# L298_Motor_Driver.net
KiCad netlist of a schematic drawn in EAGLE
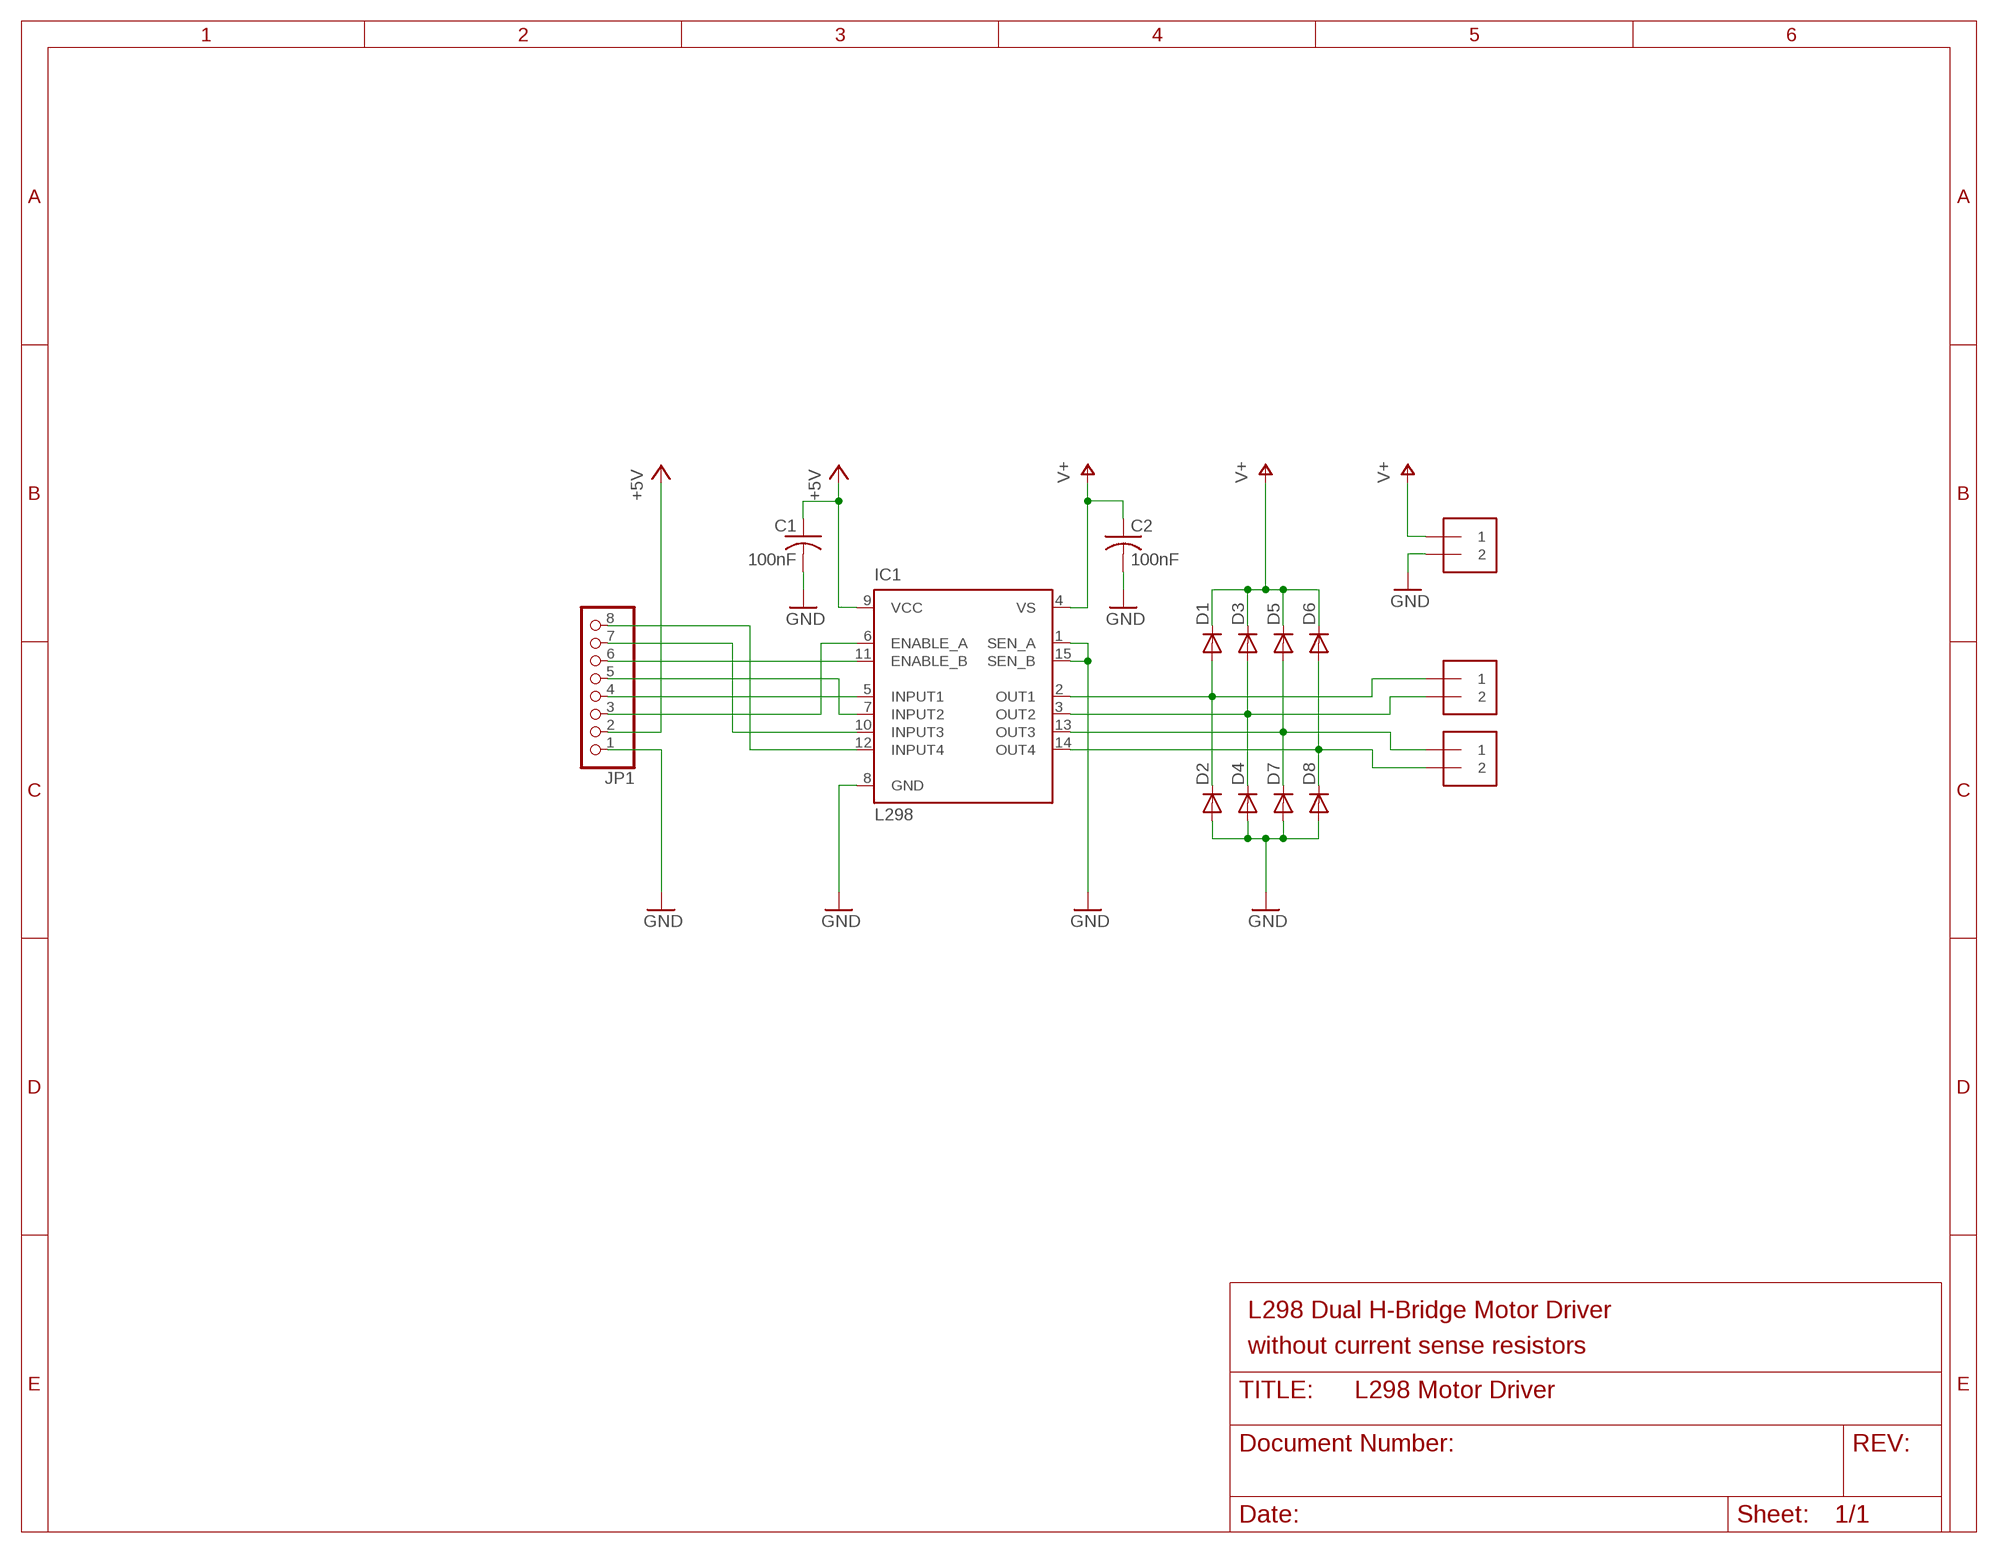
[diagram p0: schematic, sheet 1]

(export (version "E")
  (design (tool "Eeschema 10.0.6"))
  (components
    (comp (ref "C1")
      (value "100nF")
      (footprint "eagle-import:C050-024X044")
      (libsource (lib "eagle-import") (part "C-US050-024X044"))
    )
    (comp (ref "C2")
      (value "100nF")
      (footprint "eagle-import:C050-024X044")
      (libsource (lib "eagle-import") (part "C-US050-024X044"))
    )
    (comp (ref "D1")
      (value "DIODE-D-5")
      (footprint "eagle-import:D-5")
      (libsource (lib "eagle-import") (part "DIODE-D-5"))
    )
    (comp (ref "D2")
      (value "DIODE-D-5")
      (footprint "eagle-import:D-5")
      (libsource (lib "eagle-import") (part "DIODE-D-5"))
    )
    (comp (ref "D3")
      (value "DIODE-D-5")
      (footprint "eagle-import:D-5")
      (libsource (lib "eagle-import") (part "DIODE-D-5"))
    )
    (comp (ref "D4")
      (value "DIODE-D-5")
      (footprint "eagle-import:D-5")
      (libsource (lib "eagle-import") (part "DIODE-D-5"))
    )
    (comp (ref "D5")
      (value "DIODE-D-5")
      (footprint "eagle-import:D-5")
      (libsource (lib "eagle-import") (part "DIODE-D-5"))
    )
    (comp (ref "D6")
      (value "DIODE-D-5")
      (footprint "eagle-import:D-5")
      (libsource (lib "eagle-import") (part "DIODE-D-5"))
    )
    (comp (ref "D7")
      (value "DIODE-D-5")
      (footprint "eagle-import:D-5")
      (libsource (lib "eagle-import") (part "DIODE-D-5"))
    )
    (comp (ref "D8")
      (value "DIODE-D-5")
      (footprint "eagle-import:D-5")
      (libsource (lib "eagle-import") (part "DIODE-D-5"))
    )
    (comp (ref "IC1")
      (value "L298")
      (footprint "eagle-import:MULTIWATT-15")
      (fields (field (name "MPN") "L298N"))
      (libsource (lib "eagle-import") (part "L298"))
    )
    (comp (ref "J1")
      (value "1X2-3.5MM")
      (footprint "eagle-import:1X2-3.5MM")
      (libsource (lib "eagle-import") (part "1X2-3.5MM"))
    )
    (comp (ref "J2")
      (value "1X2-3.5MM")
      (footprint "eagle-import:1X2-3.5MM")
      (libsource (lib "eagle-import") (part "1X2-3.5MM"))
    )
    (comp (ref "J3")
      (value "1X2-3.5MM")
      (footprint "eagle-import:1X2-3.5MM")
      (libsource (lib "eagle-import") (part "1X2-3.5MM"))
    )
    (comp (ref "JP1")
      (value "PINHD-1X8")
      (footprint "eagle-import:1X08")
      (libsource (lib "eagle-import") (part "PINHD-1X8"))
    )
  )
  (nets
    (net (code "1") (name "+5V") (class "Default")
      (node (ref "C1") (pin "1") (pinfunction "1_1") (pintype "passive"))
      (node (ref "IC1") (pin "9") (pinfunction "VCC_9") (pintype "power_in"))
      (node (ref "JP1") (pin "2") (pinfunction "2_2") (pintype "passive"))
    )
    (net (code "2") (name "GND") (class "Default")
      (node (ref "C1") (pin "2") (pinfunction "2_2") (pintype "passive"))
      (node (ref "C2") (pin "2") (pinfunction "2_2") (pintype "passive"))
      (node (ref "D2") (pin "A") (pinfunction "A_A") (pintype "passive"))
      (node (ref "D4") (pin "A") (pinfunction "A_A") (pintype "passive"))
      (node (ref "D7") (pin "A") (pinfunction "A_A") (pintype "passive"))
      (node (ref "D8") (pin "A") (pinfunction "A_A") (pintype "passive"))
      (node (ref "IC1") (pin "1") (pinfunction "SEN_A_1") (pintype "input"))
      (node (ref "IC1") (pin "15") (pinfunction "SEN_B_15") (pintype "input"))
      (node (ref "IC1") (pin "8") (pinfunction "GND_8") (pintype "power_in"))
      (node (ref "J1") (pin "2") (pinfunction "2_2") (pintype "passive"))
      (node (ref "JP1") (pin "1") (pinfunction "1_1") (pintype "passive"))
    )
    (net (code "3") (name "Net-(IC1-ENABLE_A)") (class "Default")
      (node (ref "IC1") (pin "6") (pinfunction "ENABLE_A_6") (pintype "input"))
      (node (ref "JP1") (pin "3") (pinfunction "3_3") (pintype "passive"))
    )
    (net (code "4") (name "Net-(IC1-ENABLE_B)") (class "Default")
      (node (ref "IC1") (pin "11") (pinfunction "ENABLE_B_11") (pintype "input"))
      (node (ref "JP1") (pin "6") (pinfunction "6_6") (pintype "passive"))
    )
    (net (code "5") (name "Net-(IC1-INPUT1)") (class "Default")
      (node (ref "IC1") (pin "5") (pinfunction "INPUT1_5") (pintype "input"))
      (node (ref "JP1") (pin "4") (pinfunction "4_4") (pintype "passive"))
    )
    (net (code "6") (name "Net-(IC1-INPUT2)") (class "Default")
      (node (ref "IC1") (pin "7") (pinfunction "INPUT2_7") (pintype "input"))
      (node (ref "JP1") (pin "5") (pinfunction "5_5") (pintype "passive"))
    )
    (net (code "7") (name "Net-(IC1-INPUT3)") (class "Default")
      (node (ref "IC1") (pin "10") (pinfunction "INPUT3_10") (pintype "input"))
      (node (ref "JP1") (pin "7") (pinfunction "7_7") (pintype "passive"))
    )
    (net (code "8") (name "Net-(IC1-INPUT4)") (class "Default")
      (node (ref "IC1") (pin "12") (pinfunction "INPUT4_12") (pintype "input"))
      (node (ref "JP1") (pin "8") (pinfunction "8_8") (pintype "passive"))
    )
    (net (code "9") (name "Net-(IC1-OUT1)") (class "Default")
      (node (ref "D1") (pin "A") (pinfunction "A_A") (pintype "passive"))
      (node (ref "D2") (pin "C") (pinfunction "C_C") (pintype "passive"))
      (node (ref "IC1") (pin "2") (pinfunction "OUT1_2") (pintype "output"))
      (node (ref "J2") (pin "1") (pinfunction "1_1") (pintype "passive"))
    )
    (net (code "10") (name "Net-(IC1-OUT2)") (class "Default")
      (node (ref "D3") (pin "A") (pinfunction "A_A") (pintype "passive"))
      (node (ref "D4") (pin "C") (pinfunction "C_C") (pintype "passive"))
      (node (ref "IC1") (pin "3") (pinfunction "OUT2_3") (pintype "output"))
      (node (ref "J2") (pin "2") (pinfunction "2_2") (pintype "passive"))
    )
    (net (code "11") (name "Net-(IC1-OUT3)") (class "Default")
      (node (ref "D5") (pin "A") (pinfunction "A_A") (pintype "passive"))
      (node (ref "D7") (pin "C") (pinfunction "C_C") (pintype "passive"))
      (node (ref "IC1") (pin "13") (pinfunction "OUT3_13") (pintype "output"))
      (node (ref "J3") (pin "1") (pinfunction "1_1") (pintype "passive"))
    )
    (net (code "12") (name "Net-(IC1-OUT4)") (class "Default")
      (node (ref "D6") (pin "A") (pinfunction "A_A") (pintype "passive"))
      (node (ref "D8") (pin "C") (pinfunction "C_C") (pintype "passive"))
      (node (ref "IC1") (pin "14") (pinfunction "OUT4_14") (pintype "output"))
      (node (ref "J3") (pin "2") (pinfunction "2_2") (pintype "passive"))
    )
    (net (code "13") (name "V+") (class "Default")
      (node (ref "C2") (pin "1") (pinfunction "1_1") (pintype "passive"))
      (node (ref "D1") (pin "C") (pinfunction "C_C") (pintype "passive"))
      (node (ref "D3") (pin "C") (pinfunction "C_C") (pintype "passive"))
      (node (ref "D5") (pin "C") (pinfunction "C_C") (pintype "passive"))
      (node (ref "D6") (pin "C") (pinfunction "C_C") (pintype "passive"))
      (node (ref "IC1") (pin "4") (pinfunction "VS_4") (pintype "power_in"))
      (node (ref "J1") (pin "1") (pinfunction "1_1") (pintype "passive"))
    )
  )
)
